# Laser_Harp_Top.net
KiCad netlist of a schematic drawn in Altium Designer
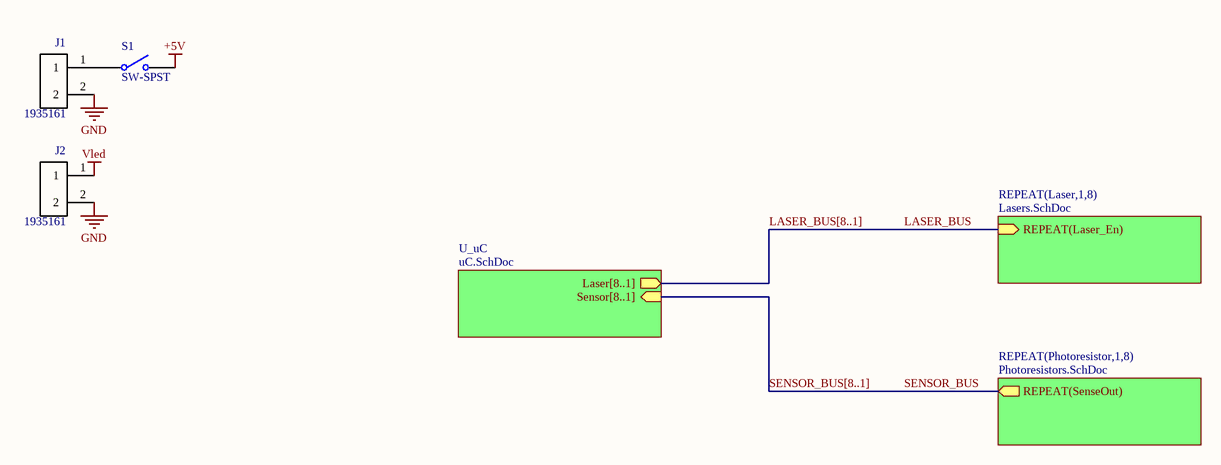
[diagram p0: Laser_Harp_Top.SchDoc]

(export (version "E")
  (design (tool "Eeschema 10.0.6"))
  (components
    (comp (ref "J1")
      (value "1935161")
      (footprint "PHOENIX_1935161")
      (description "Conn Terminal Blocks 2 POS 5mm Solder ST Thru-Hole 16A")
      (fields (field (name "DIGI-KEY_PART_NUMBER") "277-1667-ND") (field (name "MF") "Phoenix Contact"))
      (libsource (lib "Laser") (part "1935161"))
    )
    (comp (ref "J2")
      (value "1935161")
      (footprint "PHOENIX_1935161")
      (description "Conn Terminal Blocks 2 POS 5mm Solder ST Thru-Hole 16A")
      (fields (field (name "DIGI-KEY_PART_NUMBER") "277-1667-ND") (field (name "MF") "Phoenix Contact"))
      (libsource (lib "Laser") (part "1935161"))
    )
    (comp (ref "S1")
      (value "SW-SPST")
      (footprint "SPST-2")
      (description "Single-Pole, Single-Throw Switch")
      (fields (field (name "PUBLISHER") "Altium Limited"))
      (libsource (lib "Miscellaneous Devices") (part "SW-SPST"))
    )
  )
  (nets
    (net (code "17") (name "+5V") (class "Default")
      (node (ref "S1") (pin "2") (pinfunction "NO_2") (pintype "passive"))
    )
    (net (code "22") (name "GND") (class "Default")
      (node (ref "J1") (pin "2") (pinfunction "2_2") (pintype "passive"))
      (node (ref "J2") (pin "2") (pinfunction "2_2") (pintype "passive"))
    )
    (net (code "23") (name "Net-(S1-COMMON)") (class "Default")
      (node (ref "J1") (pin "1") (pinfunction "1_1") (pintype "passive"))
      (node (ref "S1") (pin "1") (pinfunction "COMMON_1") (pintype "passive"))
    )
    (net (code "24") (name "Vled") (class "Default")
      (node (ref "J2") (pin "1") (pinfunction "1_1") (pintype "passive"))
    )
  )
)
